# ESP12_RGBW_01.net
KiCad netlist of a schematic drawn in Altium Designer
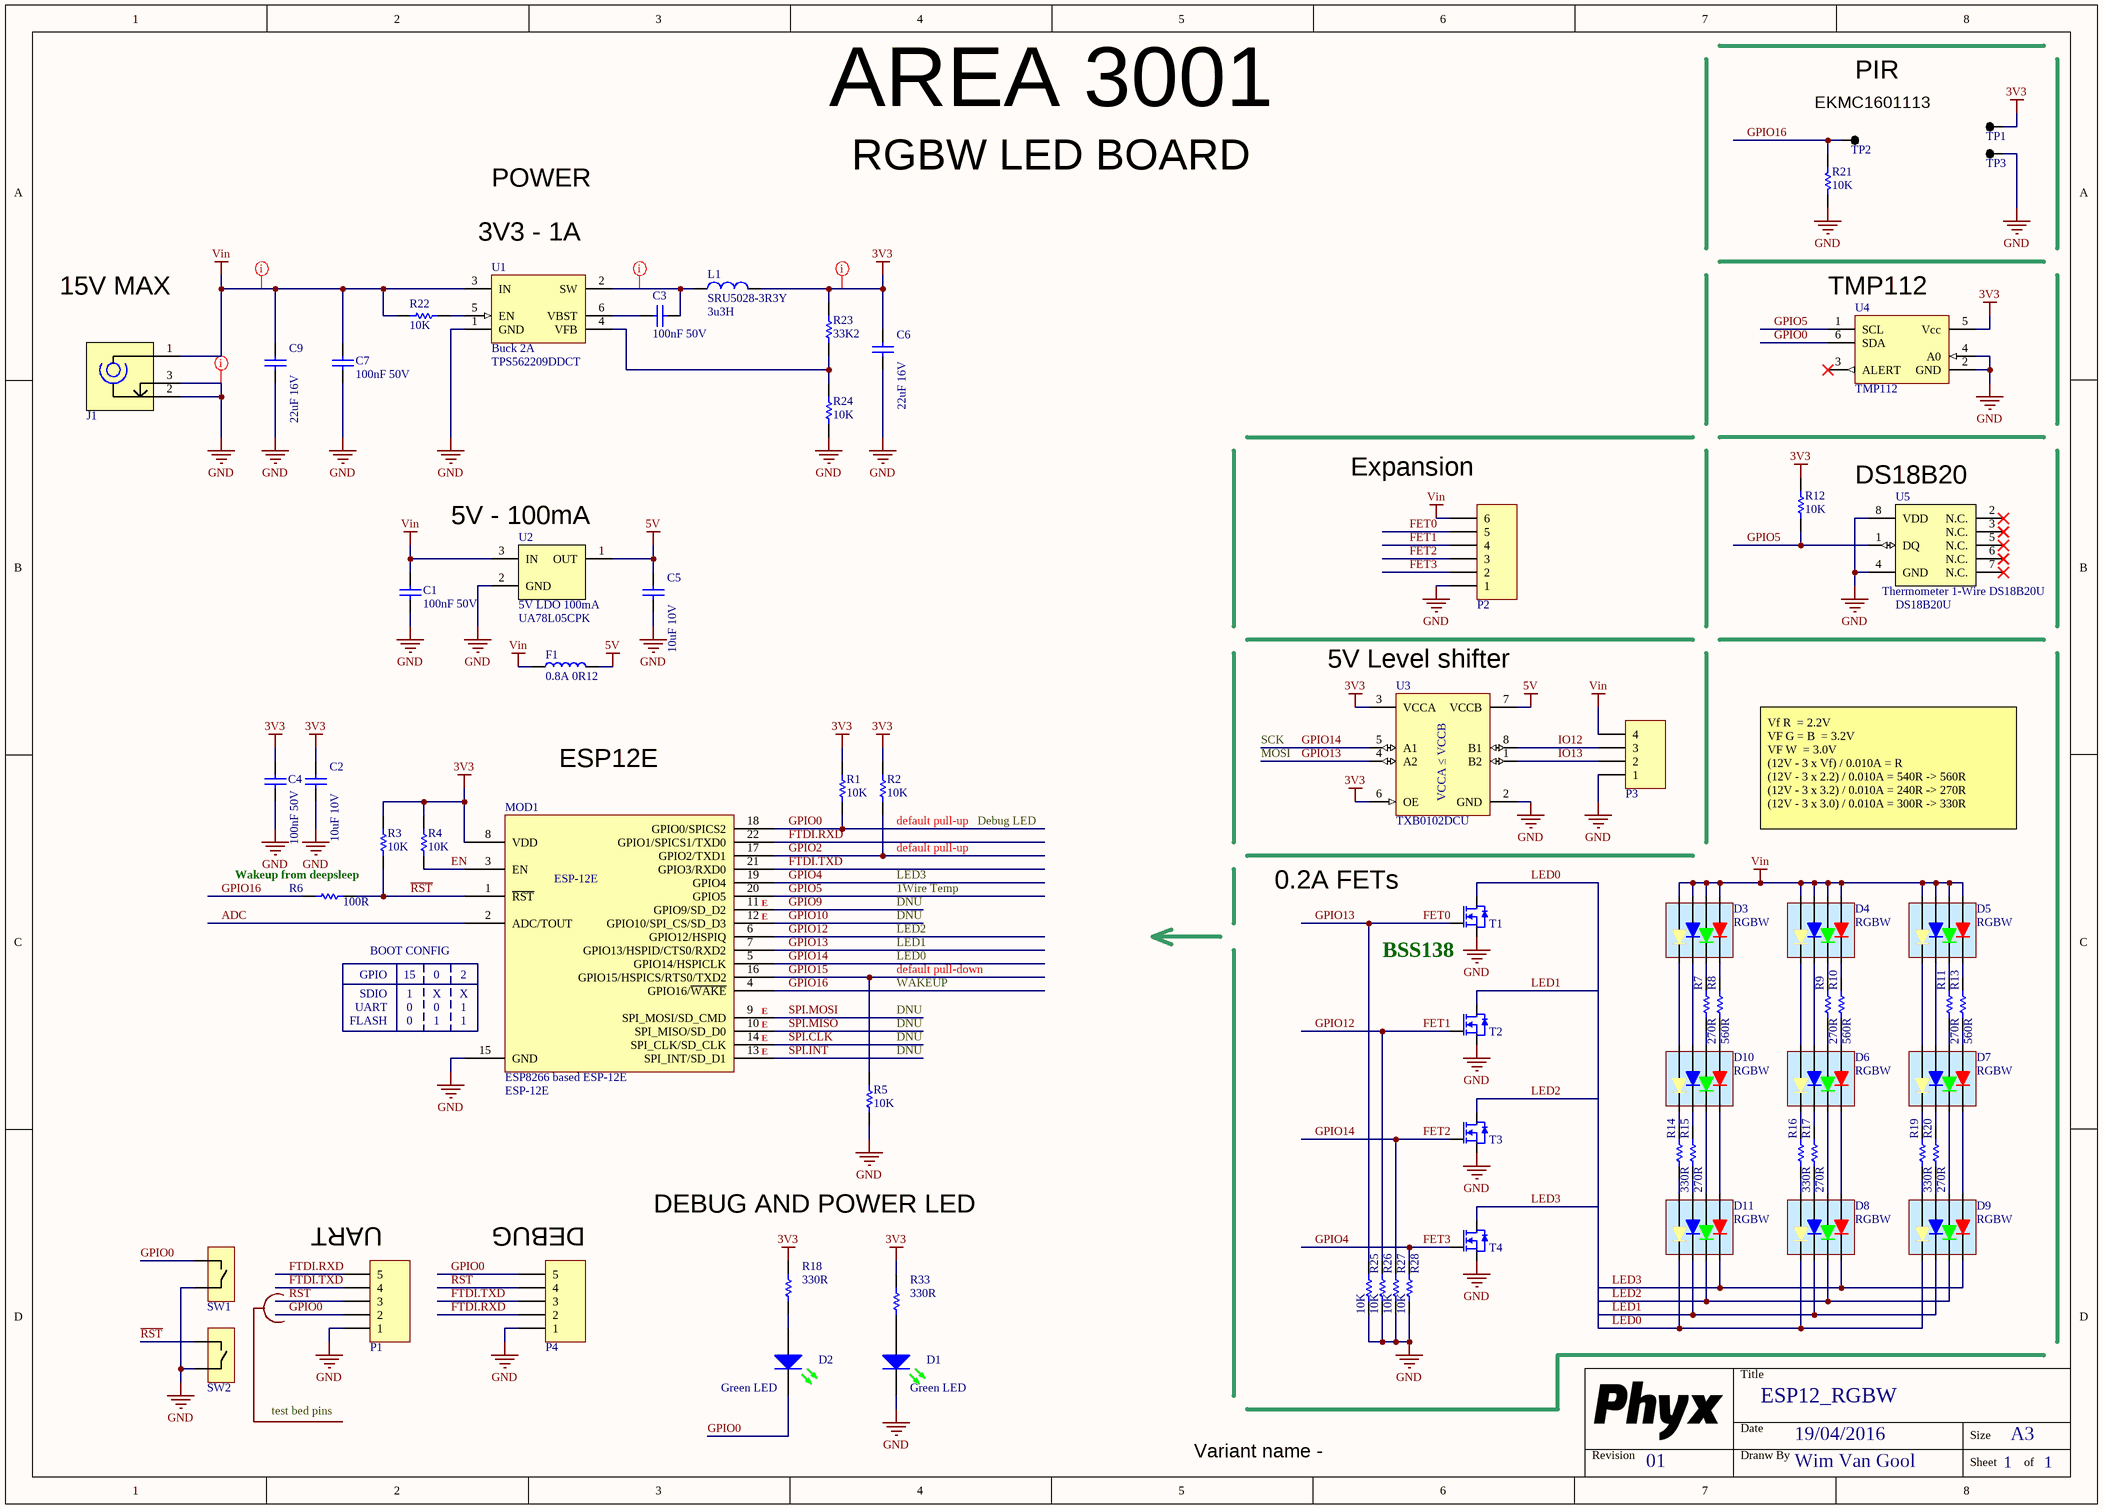
[diagram p0: ESP12_RGBW_01.SchDoc]

(export (version "E")
  (design (tool "Eeschema 10.0.6"))
  (components
    (comp (ref "C1")
      (value "100nF 50V")
      (footprint "C0603_N")
      (description "Capacitor Ceramic")
      (fields (field (name "Comment") "CAP_CERAMIC"))
      (libsource (lib "Phyx_Components") (part "CAP_CERAMIC"))
    )
    (comp (ref "C2")
      (value "10uF 10V")
      (footprint "C0805_N")
      (description "Capacitor Ceramic")
      (fields (field (name "Comment") "CAP_CERAMIC"))
      (libsource (lib "Phyx_Components") (part "CAP_CERAMIC"))
    )
    (comp (ref "C3")
      (value "100nF 50V")
      (footprint "C0603_N")
      (description "Capacitor Ceramic")
      (fields (field (name "Comment") "CAP_CERAMIC"))
      (libsource (lib "Phyx_Components") (part "CAP_CERAMIC"))
    )
    (comp (ref "C4")
      (value "100nF 50V")
      (footprint "C0603_N")
      (description "Capacitor Ceramic")
      (fields (field (name "Comment") "CAP_CERAMIC"))
      (libsource (lib "Phyx_Components") (part "CAP_CERAMIC"))
    )
    (comp (ref "C5")
      (value "10uF 10V")
      (footprint "C0805_N")
      (description "Capacitor Ceramic")
      (fields (field (name "Comment") "CAP_CERAMIC"))
      (libsource (lib "Phyx_Components") (part "CAP_CERAMIC"))
    )
    (comp (ref "C6")
      (value "22uF 16V")
      (footprint "C1206_N")
      (description "Capacitor Ceramic")
      (fields (field (name "Comment") "CAP_CERAMIC"))
      (libsource (lib "Phyx_Components") (part "CAP_CERAMIC"))
    )
    (comp (ref "C7")
      (value "100nF 50V")
      (footprint "C0603_N")
      (description "Capacitor Ceramic")
      (fields (field (name "Comment") "CAP_CERAMIC"))
      (libsource (lib "Phyx_Components") (part "CAP_CERAMIC"))
    )
    (comp (ref "C9")
      (value "22uF 16V")
      (footprint "C1206_N")
      (description "Capacitor Ceramic")
      (fields (field (name "Comment") "CAP_CERAMIC"))
      (libsource (lib "Phyx_Components") (part "CAP_CERAMIC"))
    )
    (comp (ref "D1")
      (value "Green LED")
      (footprint "LED_0805_GR")
      (description "=Description")
      (libsource (lib "Phyx_Components") (part "LED_GREEN"))
    )
    (comp (ref "D2")
      (value "Green LED")
      (footprint "LED_0805_GR")
      (description "=Description")
      (libsource (lib "Phyx_Components") (part "LED_GREEN"))
    )
    (comp (ref "D3")
      (value "RGBW")
      (footprint "LED_5050_RGBW_PLCC8")
      (description "=Description")
      (fields (field (name "Comment") "5050 RGBW LED"))
      (libsource (lib "Phyx_Components") (part "LED_RGBW"))
    )
    (comp (ref "D4")
      (value "RGBW")
      (footprint "LED_5050_RGBW_PLCC8")
      (description "=Description")
      (fields (field (name "Comment") "5050 RGBW LED"))
      (libsource (lib "Phyx_Components") (part "LED_RGBW"))
    )
    (comp (ref "D5")
      (value "RGBW")
      (footprint "LED_5050_RGBW_PLCC8")
      (description "=Description")
      (fields (field (name "Comment") "5050 RGBW LED"))
      (libsource (lib "Phyx_Components") (part "LED_RGBW"))
    )
    (comp (ref "D6")
      (value "RGBW")
      (footprint "LED_5050_RGBW_PLCC8")
      (description "=Description")
      (fields (field (name "Comment") "5050 RGBW LED"))
      (libsource (lib "Phyx_Components") (part "LED_RGBW"))
    )
    (comp (ref "D7")
      (value "RGBW")
      (footprint "LED_5050_RGBW_PLCC8")
      (description "=Description")
      (fields (field (name "Comment") "5050 RGBW LED"))
      (libsource (lib "Phyx_Components") (part "LED_RGBW"))
    )
    (comp (ref "D8")
      (value "RGBW")
      (footprint "LED_5050_RGBW_PLCC8")
      (description "=Description")
      (fields (field (name "Comment") "5050 RGBW LED"))
      (libsource (lib "Phyx_Components") (part "LED_RGBW"))
    )
    (comp (ref "D9")
      (value "RGBW")
      (footprint "LED_5050_RGBW_PLCC8")
      (description "=Description")
      (fields (field (name "Comment") "5050 RGBW LED"))
      (libsource (lib "Phyx_Components") (part "LED_RGBW"))
    )
    (comp (ref "D10")
      (value "RGBW")
      (footprint "LED_5050_RGBW_PLCC8")
      (description "=Description")
      (fields (field (name "Comment") "5050 RGBW LED"))
      (libsource (lib "Phyx_Components") (part "LED_RGBW"))
    )
    (comp (ref "D11")
      (value "RGBW")
      (footprint "LED_5050_RGBW_PLCC8")
      (description "=Description")
      (fields (field (name "Comment") "5050 RGBW LED"))
      (libsource (lib "Phyx_Components") (part "LED_RGBW"))
    )
    (comp (ref "F1")
      (value "0.8A 0R12")
      (footprint "L0805")
      (fields (field (name "Comment") "FERRITE"))
      (libsource (lib "Phyx_Components") (part "FERRITE"))
    )
    (comp (ref "J1")
      (value "Socket RA 3.5 with 1.35 barrel")
      (footprint "DC-003")
      (description "SCKT 1.35mm barrel 3.5mm dia")
      (libsource (lib "Phyx_Components") (part "Cliff_DC10"))
    )
    (comp (ref "L1")
      (value "SRU5028-3R3Y")
      (footprint "BRNS_SRU5028")
      (fields (field (name "ALTIUM_VALUE") "3u3H"))
      (libsource (lib "Phyx_Components") (part "INDUCTOR"))
    )
    (comp (ref "MOD1")
      (value "ESP8266 based ESP-12E")
      (footprint "ESP-12E")
      (description "=Description")
      (fields (field (name "ALTIUM_VALUE") "ESP-12E"))
      (libsource (lib "Phyx_Components") (part "ESP-12E"))
    )
    (comp (ref "P1")
      (value "Header 5")
      (footprint "HDR1X5")
      (libsource (lib "Phyx_Components") (part "Header 5"))
    )
    (comp (ref "P2")
      (value "Header 6")
      (footprint "HDR1X6")
      (libsource (lib "Phyx_Components") (part "Header 6"))
    )
    (comp (ref "P3")
      (value "Header 4")
      (footprint "HDR1X4")
      (libsource (lib "Phyx_Components") (part "Header 4"))
    )
    (comp (ref "P4")
      (value "Header 1.0mm RA Shrouded 5")
      (footprint "WE_665105131822")
      (libsource (lib "Phyx_Components") (part "Header 5"))
    )
    (comp (ref "R1")
      (value "10K")
      (footprint "R0603_N")
      (fields (field (name "Comment") "RESISTOR"))
      (libsource (lib "Phyx_Components") (part "RESISTOR"))
    )
    (comp (ref "R2")
      (value "10K")
      (footprint "R0603_N")
      (fields (field (name "Comment") "RESISTOR"))
      (libsource (lib "Phyx_Components") (part "RESISTOR"))
    )
    (comp (ref "R3")
      (value "10K")
      (footprint "R0603_N")
      (fields (field (name "Comment") "RESISTOR"))
      (libsource (lib "Phyx_Components") (part "RESISTOR"))
    )
    (comp (ref "R4")
      (value "10K")
      (footprint "R0603_N")
      (fields (field (name "Comment") "RESISTOR"))
      (libsource (lib "Phyx_Components") (part "RESISTOR"))
    )
    (comp (ref "R5")
      (value "10K")
      (footprint "R0603_N")
      (fields (field (name "Comment") "RESISTOR"))
      (libsource (lib "Phyx_Components") (part "RESISTOR"))
    )
    (comp (ref "R6")
      (value "100R")
      (footprint "R0603_N")
      (fields (field (name "Comment") "RESISTOR"))
      (libsource (lib "Phyx_Components") (part "RESISTOR"))
    )
    (comp (ref "R7")
      (value "270R")
      (footprint "R0603_N")
      (fields (field (name "Comment") "RESISTOR"))
      (libsource (lib "Phyx_Components") (part "RESISTOR"))
    )
    (comp (ref "R8")
      (value "560R")
      (footprint "R0603_N")
      (fields (field (name "Comment") "RESISTOR"))
      (libsource (lib "Phyx_Components") (part "RESISTOR"))
    )
    (comp (ref "R9")
      (value "270R")
      (footprint "R0603_N")
      (fields (field (name "Comment") "RESISTOR"))
      (libsource (lib "Phyx_Components") (part "RESISTOR"))
    )
    (comp (ref "R10")
      (value "560R")
      (footprint "R0603_N")
      (fields (field (name "Comment") "RESISTOR"))
      (libsource (lib "Phyx_Components") (part "RESISTOR"))
    )
    (comp (ref "R11")
      (value "270R")
      (footprint "R0603_N")
      (fields (field (name "Comment") "RESISTOR"))
      (libsource (lib "Phyx_Components") (part "RESISTOR"))
    )
    (comp (ref "R12")
      (value "10K")
      (footprint "R0603_N")
      (fields (field (name "Comment") "RESISTOR"))
      (libsource (lib "Phyx_Components") (part "RESISTOR"))
    )
    (comp (ref "R13")
      (value "560R")
      (footprint "R0603_N")
      (fields (field (name "Comment") "RESISTOR"))
      (libsource (lib "Phyx_Components") (part "RESISTOR"))
    )
    (comp (ref "R14")
      (value "330R")
      (footprint "R0603_N")
      (fields (field (name "Comment") "RESISTOR"))
      (libsource (lib "Phyx_Components") (part "RESISTOR"))
    )
    (comp (ref "R15")
      (value "270R")
      (footprint "R0603_N")
      (fields (field (name "Comment") "RESISTOR"))
      (libsource (lib "Phyx_Components") (part "RESISTOR"))
    )
    (comp (ref "R16")
      (value "330R")
      (footprint "R0603_N")
      (fields (field (name "Comment") "RESISTOR"))
      (libsource (lib "Phyx_Components") (part "RESISTOR"))
    )
    (comp (ref "R17")
      (value "270R")
      (footprint "R0603_N")
      (fields (field (name "Comment") "RESISTOR"))
      (libsource (lib "Phyx_Components") (part "RESISTOR"))
    )
    (comp (ref "R18")
      (value "330R")
      (footprint "R0603_N")
      (fields (field (name "Comment") "RESISTOR"))
      (libsource (lib "Phyx_Components") (part "RESISTOR"))
    )
    (comp (ref "R19")
      (value "330R")
      (footprint "R0603_N")
      (fields (field (name "Comment") "RESISTOR"))
      (libsource (lib "Phyx_Components") (part "RESISTOR"))
    )
    (comp (ref "R20")
      (value "270R")
      (footprint "R0603_N")
      (fields (field (name "Comment") "RESISTOR"))
      (libsource (lib "Phyx_Components") (part "RESISTOR"))
    )
    (comp (ref "R21")
      (value "10K")
      (footprint "R0603_N")
      (fields (field (name "Comment") "RESISTOR"))
      (libsource (lib "Phyx_Components") (part "RESISTOR"))
    )
    (comp (ref "R22")
      (value "10K")
      (footprint "R0603_N")
      (fields (field (name "Comment") "RESISTOR"))
      (libsource (lib "Phyx_Components") (part "RESISTOR"))
    )
    (comp (ref "R23")
      (value "33K2")
      (footprint "R0603_N")
      (fields (field (name "Comment") "RESISTOR"))
      (libsource (lib "Phyx_Components") (part "RESISTOR"))
    )
    (comp (ref "R24")
      (value "10K")
      (footprint "R0603_N")
      (fields (field (name "Comment") "RESISTOR"))
      (libsource (lib "Phyx_Components") (part "RESISTOR"))
    )
    (comp (ref "R25")
      (value "10K")
      (footprint "R0603_N")
      (fields (field (name "Comment") "RESISTOR"))
      (libsource (lib "Phyx_Components") (part "RESISTOR"))
    )
    (comp (ref "R26")
      (value "10K")
      (footprint "R0603_N")
      (fields (field (name "Comment") "RESISTOR"))
      (libsource (lib "Phyx_Components") (part "RESISTOR"))
    )
    (comp (ref "R27")
      (value "10K")
      (footprint "R0603_N")
      (fields (field (name "Comment") "RESISTOR"))
      (libsource (lib "Phyx_Components") (part "RESISTOR"))
    )
    (comp (ref "R28")
      (value "10K")
      (footprint "R0603_N")
      (fields (field (name "Comment") "RESISTOR"))
      (libsource (lib "Phyx_Components") (part "RESISTOR"))
    )
    (comp (ref "R33")
      (value "330R")
      (footprint "R0603_N")
      (fields (field (name "Comment") "RESISTOR"))
      (libsource (lib "Phyx_Components") (part "RESISTOR"))
    )
    (comp (ref "SW1")
      (value "LP SMD tact sw")
      (footprint "CK_KMR4")
      (libsource (lib "Phyx_Components") (part "SW_TACT"))
    )
    (comp (ref "SW2")
      (value "LP SMD tact sw")
      (footprint "CK_KMR4")
      (libsource (lib "Phyx_Components") (part "SW_TACT"))
    )
    (comp (ref "T1")
      (value "0.2A N-Ch MOSFET Vgs 3.2")
      (footprint "SOT23-3")
      (description "BSS138 N-Ch MOSFET 0.2A 3.2Vgs 60Vds")
      (libsource (lib "Phyx_Components") (part "N_MOSFET_GSD"))
    )
    (comp (ref "T2")
      (value "0.2A N-Ch MOSFET Vgs 3.2")
      (footprint "SOT23-3")
      (description "BSS138 N-Ch MOSFET 0.2A 3.2Vgs 60Vds")
      (libsource (lib "Phyx_Components") (part "N_MOSFET_GSD"))
    )
    (comp (ref "T3")
      (value "0.2A N-Ch MOSFET Vgs 3.2")
      (footprint "SOT23-3")
      (description "BSS138 N-Ch MOSFET 0.2A 3.2Vgs 60Vds")
      (libsource (lib "Phyx_Components") (part "N_MOSFET_GSD"))
    )
    (comp (ref "T4")
      (value "0.2A N-Ch MOSFET Vgs 3.2")
      (footprint "SOT23-3")
      (description "BSS138 N-Ch MOSFET 0.2A 3.2Vgs 60Vds")
      (libsource (lib "Phyx_Components") (part "N_MOSFET_GSD"))
    )
    (comp (ref "TP1")
      (value "TEST_PAD")
      (footprint "TP_0.8mm_0.4mm")
      (libsource (lib "Phyx_Components") (part "TEST_PAD"))
    )
    (comp (ref "TP2")
      (value "TEST_PAD")
      (footprint "TP_0.8mm_0.4mm")
      (libsource (lib "Phyx_Components") (part "TEST_PAD"))
    )
    (comp (ref "TP3")
      (value "TEST_PAD")
      (footprint "TP_0.8mm_0.4mm")
      (libsource (lib "Phyx_Components") (part "TEST_PAD"))
    )
    (comp (ref "U1")
      (value "Buck 2A")
      (footprint "TI_DDC_R-PDSO-G6")
      (description "=Description")
      (fields (field (name "ALTIUM_VALUE") "TPS562209DDCT"))
      (libsource (lib "Phyx_Components") (part "TPS56x209"))
    )
    (comp (ref "U2")
      (value "5V LDO 100mA")
      (footprint "TI_PK")
      (description "LDO 5V 100mA")
      (fields (field (name "ALTIUM_VALUE") "UA78L05CPK"))
      (libsource (lib "Phyx_Components") (part "UA78L05CPK"))
    )
    (comp (ref "U3")
      (value "TXB0102DCU")
      (footprint "TI_DCU_R-PDSO-G8")
      (description "=Description")
      (fields (field (name "Comment") "2-bit Bi Level translator, 15kV ESD"))
      (libsource (lib "Phyx_Components") (part "TXB0102DCU"))
    )
    (comp (ref "U4")
      (value "TMP112")
      (footprint "TI_DRL_R-PDSO-N6")
      (description "=Description")
      (fields (field (name "Comment") "I2C Temp sensor High Accuracy"))
      (libsource (lib "Phyx_Components") (part "TMP1x2"))
    )
    (comp (ref "U5")
      (value "Thermometer 1-Wire DS18B20U")
      (footprint "MAX_uSOP8")
      (description "=Description")
      (fields (field (name "ALTIUM_VALUE") "DS18B20U"))
      (libsource (lib "Phyx_Components") (part "DS18B20U"))
    )
  )
  (nets
    (net (code "1") (name "/ADC") (class "Default")
      (node (ref "MOD1") (pin "2") (pinfunction "ADC/TOUT_2") (pintype "passive"))
    )
    (net (code "2") (name "/EN") (class "Default")
      (node (ref "MOD1") (pin "3") (pinfunction "EN_3") (pintype "passive"))
      (node (ref "R4") (pin "2") (pinfunction "2_2") (pintype "passive"))
    )
    (net (code "3") (name "/FET0") (class "Default")
      (node (ref "MOD1") (pin "7") (pinfunction "GPIO13/HSPID/CTS0/RXD2_7") (pintype "passive"))
      (node (ref "P2") (pin "5") (pinfunction "5_5") (pintype "passive"))
      (node (ref "R25") (pin "1") (pinfunction "1_1") (pintype "passive"))
      (node (ref "T1") (pin "1") (pinfunction "G_1") (pintype "passive"))
      (node (ref "U3") (pin "4") (pinfunction "A2_4") (pintype "bidirectional"))
    )
    (net (code "4") (name "/FET1") (class "Default")
      (node (ref "MOD1") (pin "6") (pinfunction "GPIO12/HSPIQ_6") (pintype "passive"))
      (node (ref "P2") (pin "4") (pinfunction "4_4") (pintype "passive"))
      (node (ref "R26") (pin "1") (pinfunction "1_1") (pintype "passive"))
      (node (ref "T2") (pin "1") (pinfunction "G_1") (pintype "passive"))
    )
    (net (code "5") (name "/FET2") (class "Default")
      (node (ref "MOD1") (pin "5") (pinfunction "GPIO14/HSPICLK_5") (pintype "passive"))
      (node (ref "P2") (pin "3") (pinfunction "3_3") (pintype "passive"))
      (node (ref "R27") (pin "1") (pinfunction "1_1") (pintype "passive"))
      (node (ref "T3") (pin "1") (pinfunction "G_1") (pintype "passive"))
      (node (ref "U3") (pin "5") (pinfunction "A1_5") (pintype "bidirectional"))
    )
    (net (code "6") (name "/FET3") (class "Default")
      (node (ref "MOD1") (pin "19") (pinfunction "GPIO4_19") (pintype "passive"))
      (node (ref "P2") (pin "2") (pinfunction "2_2") (pintype "passive"))
      (node (ref "R28") (pin "1") (pinfunction "1_1") (pintype "passive"))
      (node (ref "T4") (pin "1") (pinfunction "G_1") (pintype "passive"))
    )
    (net (code "7") (name "/FTDI.RXD") (class "Default")
      (node (ref "MOD1") (pin "22") (pinfunction "GPIO1/SPICS1/TXD0_22") (pintype "passive"))
      (node (ref "P1") (pin "5") (pinfunction "5_5") (pintype "passive"))
      (node (ref "P4") (pin "2") (pinfunction "2_2") (pintype "passive"))
    )
    (net (code "8") (name "/FTDI.TXD") (class "Default")
      (node (ref "MOD1") (pin "21") (pinfunction "GPIO3/RXD0_21") (pintype "passive"))
      (node (ref "P1") (pin "4") (pinfunction "4_4") (pintype "passive"))
      (node (ref "P4") (pin "3") (pinfunction "3_3") (pintype "passive"))
    )
    (net (code "9") (name "/GPIO0") (class "Default")
      (node (ref "D2") (pin "2") (pinfunction "K_2") (pintype "passive"))
      (node (ref "MOD1") (pin "18") (pinfunction "GPIO0/SPICS2_18") (pintype "passive"))
      (node (ref "P1") (pin "2") (pinfunction "2_2") (pintype "passive"))
      (node (ref "P4") (pin "5") (pinfunction "5_5") (pintype "passive"))
      (node (ref "R1") (pin "2") (pinfunction "2_2") (pintype "passive"))
      (node (ref "SW1") (pin "1") (pinfunction "1_1") (pintype "passive"))
      (node (ref "U4") (pin "6") (pinfunction "SDA_6") (pintype "open_collector"))
    )
    (net (code "10") (name "/GPIO2") (class "Default")
      (node (ref "MOD1") (pin "17") (pinfunction "GPIO2/TXD1_17") (pintype "passive"))
      (node (ref "R2") (pin "2") (pinfunction "2_2") (pintype "passive"))
    )
    (net (code "11") (name "/GPIO5") (class "Default")
      (node (ref "MOD1") (pin "20") (pinfunction "GPIO5_20") (pintype "passive"))
      (node (ref "R12") (pin "2") (pinfunction "2_2") (pintype "passive"))
      (node (ref "U4") (pin "1") (pinfunction "SCL_1") (pintype "open_collector"))
      (node (ref "U5") (pin "1") (pinfunction "DQ_1") (pintype "bidirectional"))
    )
    (net (code "12") (name "/GPIO9") (class "Default")
      (node (ref "MOD1") (pin "11") (pinfunction "GPIO9/SD_D2_11") (pintype "passive"))
    )
    (net (code "13") (name "/GPIO10") (class "Default")
      (node (ref "MOD1") (pin "12") (pinfunction "GPIO10/SPI_CS/SD_D3_12") (pintype "passive"))
    )
    (net (code "14") (name "/GPIO15") (class "Default")
      (node (ref "MOD1") (pin "16") (pinfunction "GPIO15/HSPICS/RTS0/TXD2_16") (pintype "passive"))
      (node (ref "R5") (pin "1") (pinfunction "1_1") (pintype "passive"))
    )
    (net (code "15") (name "/GPIO16") (class "Default")
      (node (ref "MOD1") (pin "4") (pinfunction "GPIO16/~{WAKE}_4") (pintype "passive"))
      (node (ref "R21") (pin "1") (pinfunction "1_1") (pintype "passive"))
      (node (ref "R6") (pin "2") (pinfunction "2_2") (pintype "passive"))
      (node (ref "TP2") (pin "1") (pinfunction "1_1") (pintype "passive"))
    )
    (net (code "16") (name "/IO12") (class "Default")
      (node (ref "P3") (pin "3") (pinfunction "3_3") (pintype "passive"))
      (node (ref "U3") (pin "8") (pinfunction "B1_8") (pintype "bidirectional"))
    )
    (net (code "17") (name "/IO13") (class "Default")
      (node (ref "P3") (pin "2") (pinfunction "2_2") (pintype "passive"))
      (node (ref "U3") (pin "1") (pinfunction "B2_1") (pintype "bidirectional"))
    )
    (net (code "18") (name "/LED0") (class "Default")
      (node (ref "D11") (pin "8") (pinfunction "WC_8") (pintype "passive"))
      (node (ref "D8") (pin "8") (pinfunction "WC_8") (pintype "passive"))
      (node (ref "D9") (pin "8") (pinfunction "WC_8") (pintype "passive"))
      (node (ref "T1") (pin "3") (pinfunction "D_3") (pintype "passive"))
    )
    (net (code "19") (name "/LED1") (class "Default")
      (node (ref "D11") (pin "6") (pinfunction "BC_6") (pintype "passive"))
      (node (ref "D8") (pin "6") (pinfunction "BC_6") (pintype "passive"))
      (node (ref "D9") (pin "6") (pinfunction "BC_6") (pintype "passive"))
      (node (ref "T2") (pin "3") (pinfunction "D_3") (pintype "passive"))
    )
    (net (code "20") (name "/LED2") (class "Default")
      (node (ref "D11") (pin "4") (pinfunction "GC_4") (pintype "passive"))
      (node (ref "D8") (pin "4") (pinfunction "GC_4") (pintype "passive"))
      (node (ref "D9") (pin "4") (pinfunction "GC_4") (pintype "passive"))
      (node (ref "T3") (pin "3") (pinfunction "D_3") (pintype "passive"))
    )
    (net (code "21") (name "/LED3") (class "Default")
      (node (ref "D11") (pin "2") (pinfunction "RC_2") (pintype "passive"))
      (node (ref "D8") (pin "2") (pinfunction "RC_2") (pintype "passive"))
      (node (ref "D9") (pin "2") (pinfunction "RC_2") (pintype "passive"))
      (node (ref "T4") (pin "3") (pinfunction "D_3") (pintype "passive"))
    )
    (net (code "22") (name "/SPI.CLK") (class "Default")
      (node (ref "MOD1") (pin "14") (pinfunction "SPI_CLK/SD_CLK_14") (pintype "passive"))
    )
    (net (code "23") (name "/SPI.INT") (class "Default")
      (node (ref "MOD1") (pin "13") (pinfunction "SPI_INT/SD_D1_13") (pintype "passive"))
    )
    (net (code "24") (name "/SPI.MISO") (class "Default")
      (node (ref "MOD1") (pin "10") (pinfunction "SPI_MISO/SD_D0_10") (pintype "passive"))
    )
    (net (code "25") (name "/SPI.MOSI") (class "Default")
      (node (ref "MOD1") (pin "9") (pinfunction "SPI_MOSI/SD_CMD_9") (pintype "passive"))
    )
    (net (code "26") (name "/~{RST}") (class "Default")
      (node (ref "MOD1") (pin "1") (pinfunction "~{RST}_1") (pintype "passive"))
      (node (ref "P1") (pin "3") (pinfunction "3_3") (pintype "passive"))
      (node (ref "P4") (pin "4") (pinfunction "4_4") (pintype "passive"))
      (node (ref "R3") (pin "2") (pinfunction "2_2") (pintype "passive"))
      (node (ref "R6") (pin "1") (pinfunction "1_1") (pintype "passive"))
      (node (ref "SW2") (pin "1") (pinfunction "1_1") (pintype "passive"))
    )
    (net (code "27") (name "3V3") (class "Default")
      (node (ref "C2") (pin "1") (pinfunction "1_1") (pintype "passive"))
      (node (ref "C4") (pin "1") (pinfunction "1_1") (pintype "passive"))
      (node (ref "C6") (pin "1") (pinfunction "1_1") (pintype "passive"))
      (node (ref "L1") (pin "2") (pinfunction "2_2") (pintype "passive"))
      (node (ref "MOD1") (pin "8") (pinfunction "VDD_8") (pintype "passive"))
      (node (ref "R1") (pin "1") (pinfunction "1_1") (pintype "passive"))
      (node (ref "R12") (pin "1") (pinfunction "1_1") (pintype "passive"))
      (node (ref "R18") (pin "1") (pinfunction "1_1") (pintype "passive"))
      (node (ref "R2") (pin "1") (pinfunction "1_1") (pintype "passive"))
      (node (ref "R23") (pin "1") (pinfunction "1_1") (pintype "passive"))
      (node (ref "R3") (pin "1") (pinfunction "1_1") (pintype "passive"))
      (node (ref "R33") (pin "1") (pinfunction "1_1") (pintype "passive"))
      (node (ref "R4") (pin "1") (pinfunction "1_1") (pintype "passive"))
      (node (ref "TP1") (pin "1") (pinfunction "1_1") (pintype "passive"))
      (node (ref "U3") (pin "3") (pinfunction "VCCA_3") (pintype "power_in"))
      (node (ref "U3") (pin "6") (pinfunction "OE_6") (pintype "input"))
      (node (ref "U4") (pin "5") (pinfunction "Vcc_5") (pintype "power_in"))
    )
    (net (code "28") (name "5V") (class "Default")
      (node (ref "C5") (pin "1") (pinfunction "1_1") (pintype "passive"))
      (node (ref "F1") (pin "2") (pinfunction "2_2") (pintype "passive"))
      (node (ref "U2") (pin "1") (pinfunction "OUT_1") (pintype "passive"))
      (node (ref "U3") (pin "7") (pinfunction "VCCB_7") (pintype "power_in"))
    )
    (net (code "29") (name "GND") (class "Default")
      (node (ref "C1") (pin "2") (pinfunction "2_2") (pintype "passive"))
      (node (ref "C2") (pin "2") (pinfunction "2_2") (pintype "passive"))
      (node (ref "C4") (pin "2") (pinfunction "2_2") (pintype "passive"))
      (node (ref "C5") (pin "2") (pinfunction "2_2") (pintype "passive"))
      (node (ref "C6") (pin "2") (pinfunction "2_2") (pintype "passive"))
      (node (ref "C7") (pin "1") (pinfunction "1_1") (pintype "passive"))
      (node (ref "C9") (pin "2") (pinfunction "2_2") (pintype "passive"))
      (node (ref "D1") (pin "2") (pinfunction "K_2") (pintype "passive"))
      (node (ref "J1") (pin "2") (pinfunction "2_2") (pintype "passive"))
      (node (ref "J1") (pin "3") (pinfunction "3_3") (pintype "passive"))
      (node (ref "MOD1") (pin "15") (pinfunction "GND_15") (pintype "passive"))
      (node (ref "P1") (pin "1") (pinfunction "1_1") (pintype "passive"))
      (node (ref "P2") (pin "1") (pinfunction "1_1") (pintype "passive"))
      (node (ref "P3") (pin "1") (pinfunction "1_1") (pintype "passive"))
      (node (ref "P4") (pin "1") (pinfunction "1_1") (pintype "passive"))
      (node (ref "R21") (pin "2") (pinfunction "2_2") (pintype "passive"))
      (node (ref "R24") (pin "2") (pinfunction "2_2") (pintype "passive"))
      (node (ref "R25") (pin "2") (pinfunction "2_2") (pintype "passive"))
      (node (ref "R26") (pin "2") (pinfunction "2_2") (pintype "passive"))
      (node (ref "R27") (pin "2") (pinfunction "2_2") (pintype "passive"))
      (node (ref "R28") (pin "2") (pinfunction "2_2") (pintype "passive"))
      (node (ref "R5") (pin "2") (pinfunction "2_2") (pintype "passive"))
      (node (ref "SW1") (pin "2") (pinfunction "2_2") (pintype "passive"))
      (node (ref "SW2") (pin "2") (pinfunction "2_2") (pintype "passive"))
      (node (ref "T1") (pin "2") (pinfunction "S_2") (pintype "passive"))
      (node (ref "T2") (pin "2") (pinfunction "S_2") (pintype "passive"))
      (node (ref "T3") (pin "2") (pinfunction "S_2") (pintype "passive"))
      (node (ref "T4") (pin "2") (pinfunction "S_2") (pintype "passive"))
      (node (ref "TP3") (pin "1") (pinfunction "1_1") (pintype "passive"))
      (node (ref "U1") (pin "1") (pinfunction "GND_1") (pintype "power_in"))
      (node (ref "U2") (pin "2") (pinfunction "GND_2") (pintype "passive"))
      (node (ref "U3") (pin "2") (pinfunction "GND_2") (pintype "power_in"))
      (node (ref "U4") (pin "2") (pinfunction "GND_2") (pintype "power_in"))
      (node (ref "U4") (pin "4") (pinfunction "A0_4") (pintype "input"))
      (node (ref "U5") (pin "4") (pinfunction "GND_4") (pintype "power_in"))
      (node (ref "U5") (pin "8") (pinfunction "VDD_8") (pintype "power_in"))
    )
    (net (code "30") (name "Net-(D1-A)") (class "Default")
      (node (ref "D1") (pin "1") (pinfunction "A_1") (pintype "passive"))
      (node (ref "R33") (pin "2") (pinfunction "2_2") (pintype "passive"))
    )
    (net (code "31") (name "Net-(D2-A)") (class "Default")
      (node (ref "D2") (pin "1") (pinfunction "A_1") (pintype "passive"))
      (node (ref "R18") (pin "2") (pinfunction "2_2") (pintype "passive"))
    )
    (net (code "32") (name "Net-(D3-GC)") (class "Default")
      (node (ref "D3") (pin "4") (pinfunction "GC_4") (pintype "passive"))
      (node (ref "R7") (pin "1") (pinfunction "1_1") (pintype "passive"))
    )
    (net (code "33") (name "Net-(D3-RC)") (class "Default")
      (node (ref "D3") (pin "2") (pinfunction "RC_2") (pintype "passive"))
      (node (ref "R8") (pin "1") (pinfunction "1_1") (pintype "passive"))
    )
    (net (code "34") (name "Net-(D4-BC)") (class "Default")
      (node (ref "D4") (pin "6") (pinfunction "BC_6") (pintype "passive"))
      (node (ref "D6") (pin "5") (pinfunction "BA_5") (pintype "passive"))
    )
    (net (code "35") (name "Net-(D4-GC)") (class "Default")
      (node (ref "D4") (pin "4") (pinfunction "GC_4") (pintype "passive"))
      (node (ref "R9") (pin "1") (pinfunction "1_1") (pintype "passive"))
    )
    (net (code "36") (name "Net-(D4-RC)") (class "Default")
      (node (ref "D4") (pin "2") (pinfunction "RC_2") (pintype "passive"))
      (node (ref "R10") (pin "1") (pinfunction "1_1") (pintype "passive"))
    )
    (net (code "37") (name "Net-(D4-WC)") (class "Default")
      (node (ref "D4") (pin "8") (pinfunction "WC_8") (pintype "passive"))
      (node (ref "D6") (pin "7") (pinfunction "WA_7") (pintype "passive"))
    )
    (net (code "38") (name "Net-(D5-BC)") (class "Default")
      (node (ref "D5") (pin "6") (pinfunction "BC_6") (pintype "passive"))
      (node (ref "D7") (pin "5") (pinfunction "BA_5") (pintype "passive"))
    )
    (net (code "39") (name "Net-(D5-GC)") (class "Default")
      (node (ref "D5") (pin "4") (pinfunction "GC_4") (pintype "passive"))
      (node (ref "R11") (pin "1") (pinfunction "1_1") (pintype "passive"))
    )
    (net (code "40") (name "Net-(D5-RC)") (class "Default")
      (node (ref "D5") (pin "2") (pinfunction "RC_2") (pintype "passive"))
      (node (ref "R13") (pin "1") (pinfunction "1_1") (pintype "passive"))
    )
    (net (code "41") (name "Net-(D5-WC)") (class "Default")
      (node (ref "D5") (pin "8") (pinfunction "WC_8") (pintype "passive"))
      (node (ref "D7") (pin "7") (pinfunction "WA_7") (pintype "passive"))
    )
    (net (code "42") (name "Net-(D6-BC)") (class "Default")
      (node (ref "D6") (pin "6") (pinfunction "BC_6") (pintype "passive"))
      (node (ref "R17") (pin "1") (pinfunction "1_1") (pintype "passive"))
    )
    (net (code "43") (name "Net-(D6-GA)") (class "Default")
      (node (ref "D6") (pin "3") (pinfunction "GA_3") (pintype "passive"))
      (node (ref "R9") (pin "2") (pinfunction "2_2") (pintype "passive"))
    )
    (net (code "44") (name "Net-(D6-GC)") (class "Default")
      (node (ref "D6") (pin "4") (pinfunction "GC_4") (pintype "passive"))
      (node (ref "D8") (pin "3") (pinfunction "GA_3") (pintype "passive"))
    )
    (net (code "45") (name "Net-(D6-RA)") (class "Default")
      (node (ref "D6") (pin "1") (pinfunction "RA_1") (pintype "passive"))
      (node (ref "R10") (pin "2") (pinfunction "2_2") (pintype "passive"))
    )
    (net (code "46") (name "Net-(D6-RC)") (class "Default")
      (node (ref "D6") (pin "2") (pinfunction "RC_2") (pintype "passive"))
      (node (ref "D8") (pin "1") (pinfunction "RA_1") (pintype "passive"))
    )
    (net (code "47") (name "Net-(D6-WC)") (class "Default")
      (node (ref "D6") (pin "8") (pinfunction "WC_8") (pintype "passive"))
      (node (ref "R16") (pin "1") (pinfunction "1_1") (pintype "passive"))
    )
    (net (code "48") (name "Net-(D7-BC)") (class "Default")
      (node (ref "D7") (pin "6") (pinfunction "BC_6") (pintype "passive"))
      (node (ref "R20") (pin "1") (pinfunction "1_1") (pintype "passive"))
    )
    (net (code "49") (name "Net-(D7-GA)") (class "Default")
      (node (ref "D7") (pin "3") (pinfunction "GA_3") (pintype "passive"))
      (node (ref "R11") (pin "2") (pinfunction "2_2") (pintype "passive"))
    )
    (net (code "50") (name "Net-(D7-GC)") (class "Default")
      (node (ref "D7") (pin "4") (pinfunction "GC_4") (pintype "passive"))
      (node (ref "D9") (pin "3") (pinfunction "GA_3") (pintype "passive"))
    )
    (net (code "51") (name "Net-(D7-RA)") (class "Default")
      (node (ref "D7") (pin "1") (pinfunction "RA_1") (pintype "passive"))
      (node (ref "R13") (pin "2") (pinfunction "2_2") (pintype "passive"))
    )
    (net (code "52") (name "Net-(D7-RC)") (class "Default")
      (node (ref "D7") (pin "2") (pinfunction "RC_2") (pintype "passive"))
      (node (ref "D9") (pin "1") (pinfunction "RA_1") (pintype "passive"))
    )
    (net (code "53") (name "Net-(D7-WC)") (class "Default")
      (node (ref "D7") (pin "8") (pinfunction "WC_8") (pintype "passive"))
      (node (ref "R19") (pin "1") (pinfunction "1_1") (pintype "passive"))
    )
    (net (code "54") (name "Net-(D8-BA)") (class "Default")
      (node (ref "D8") (pin "5") (pinfunction "BA_5") (pintype "passive"))
      (node (ref "R17") (pin "2") (pinfunction "2_2") (pintype "passive"))
    )
    (net (code "55") (name "Net-(D8-WA)") (class "Default")
      (node (ref "D8") (pin "7") (pinfunction "WA_7") (pintype "passive"))
      (node (ref "R16") (pin "2") (pinfunction "2_2") (pintype "passive"))
    )
    (net (code "56") (name "Net-(D9-BA)") (class "Default")
      (node (ref "D9") (pin "5") (pinfunction "BA_5") (pintype "passive"))
      (node (ref "R20") (pin "2") (pinfunction "2_2") (pintype "passive"))
    )
    (net (code "57") (name "Net-(D9-WA)") (class "Default")
      (node (ref "D9") (pin "7") (pinfunction "WA_7") (pintype "passive"))
      (node (ref "R19") (pin "2") (pinfunction "2_2") (pintype "passive"))
    )
    (net (code "58") (name "Net-(D10-BA)") (class "Default")
      (node (ref "D10") (pin "5") (pinfunction "BA_5") (pintype "passive"))
      (node (ref "D3") (pin "6") (pinfunction "BC_6") (pintype "passive"))
    )
    (net (code "59") (name "Net-(D10-BC)") (class "Default")
      (node (ref "D10") (pin "6") (pinfunction "BC_6") (pintype "passive"))
      (node (ref "R15") (pin "1") (pinfunction "1_1") (pintype "passive"))
    )
    (net (code "60") (name "Net-(D10-GA)") (class "Default")
      (node (ref "D10") (pin "3") (pinfunction "GA_3") (pintype "passive"))
      (node (ref "R7") (pin "2") (pinfunction "2_2") (pintype "passive"))
    )
    (net (code "61") (name "Net-(D10-GC)") (class "Default")
      (node (ref "D10") (pin "4") (pinfunction "GC_4") (pintype "passive"))
      (node (ref "D11") (pin "3") (pinfunction "GA_3") (pintype "passive"))
    )
    (net (code "62") (name "Net-(D10-RA)") (class "Default")
      (node (ref "D10") (pin "1") (pinfunction "RA_1") (pintype "passive"))
      (node (ref "R8") (pin "2") (pinfunction "2_2") (pintype "passive"))
    )
    (net (code "63") (name "Net-(D10-RC)") (class "Default")
      (node (ref "D10") (pin "2") (pinfunction "RC_2") (pintype "passive"))
      (node (ref "D11") (pin "1") (pinfunction "RA_1") (pintype "passive"))
    )
    (net (code "64") (name "Net-(D10-WA)") (class "Default")
      (node (ref "D10") (pin "7") (pinfunction "WA_7") (pintype "passive"))
      (node (ref "D3") (pin "8") (pinfunction "WC_8") (pintype "passive"))
    )
    (net (code "65") (name "Net-(D10-WC)") (class "Default")
      (node (ref "D10") (pin "8") (pinfunction "WC_8") (pintype "passive"))
      (node (ref "R14") (pin "1") (pinfunction "1_1") (pintype "passive"))
    )
    (net (code "66") (name "Net-(D11-BA)") (class "Default")
      (node (ref "D11") (pin "5") (pinfunction "BA_5") (pintype "passive"))
      (node (ref "R15") (pin "2") (pinfunction "2_2") (pintype "passive"))
    )
    (net (code "67") (name "Net-(D11-WA)") (class "Default")
      (node (ref "D11") (pin "7") (pinfunction "WA_7") (pintype "passive"))
      (node (ref "R14") (pin "2") (pinfunction "2_2") (pintype "passive"))
    )
    (net (code "68") (name "Net-(U1-EN)") (class "Default")
      (node (ref "R22") (pin "2") (pinfunction "2_2") (pintype "passive"))
      (node (ref "U1") (pin "5") (pinfunction "EN_5") (pintype "input"))
    )
    (net (code "69") (name "Net-(U1-SW)") (class "Default")
      (node (ref "C3") (pin "2") (pinfunction "2_2") (pintype "passive"))
      (node (ref "L1") (pin "1") (pinfunction "1_1") (pintype "passive"))
      (node (ref "U1") (pin "2") (pinfunction "SW_2") (pintype "power_in"))
    )
    (net (code "70") (name "Net-(U1-VBST)") (class "Default")
      (node (ref "C3") (pin "1") (pinfunction "1_1") (pintype "passive"))
      (node (ref "U1") (pin "6") (pinfunction "VBST_6") (pintype "power_in"))
    )
    (net (code "71") (name "Net-(U1-VFB)") (class "Default")
      (node (ref "R23") (pin "2") (pinfunction "2_2") (pintype "passive"))
      (node (ref "R24") (pin "1") (pinfunction "1_1") (pintype "passive"))
      (node (ref "U1") (pin "4") (pinfunction "VFB_4") (pintype "passive"))
    )
    (net (code "72") (name "Vin") (class "Default")
      (node (ref "C1") (pin "1") (pinfunction "1_1") (pintype "passive"))
      (node (ref "C7") (pin "2") (pinfunction "2_2") (pintype "passive"))
      (node (ref "C9") (pin "1") (pinfunction "1_1") (pintype "passive"))
      (node (ref "D3") (pin "1") (pinfunction "RA_1") (pintype "passive"))
      (node (ref "D3") (pin "3") (pinfunction "GA_3") (pintype "passive"))
      (node (ref "D3") (pin "5") (pinfunction "BA_5") (pintype "passive"))
      (node (ref "D3") (pin "7") (pinfunction "WA_7") (pintype "passive"))
      (node (ref "D4") (pin "1") (pinfunction "RA_1") (pintype "passive"))
      (node (ref "D4") (pin "3") (pinfunction "GA_3") (pintype "passive"))
      (node (ref "D4") (pin "5") (pinfunction "BA_5") (pintype "passive"))
      (node (ref "D4") (pin "7") (pinfunction "WA_7") (pintype "passive"))
      (node (ref "D5") (pin "1") (pinfunction "RA_1") (pintype "passive"))
      (node (ref "D5") (pin "3") (pinfunction "GA_3") (pintype "passive"))
      (node (ref "D5") (pin "5") (pinfunction "BA_5") (pintype "passive"))
      (node (ref "D5") (pin "7") (pinfunction "WA_7") (pintype "passive"))
      (node (ref "F1") (pin "1") (pinfunction "1_1") (pintype "passive"))
      (node (ref "J1") (pin "1") (pinfunction "1_1") (pintype "passive"))
      (node (ref "P2") (pin "6") (pinfunction "6_6") (pintype "passive"))
      (node (ref "P3") (pin "4") (pinfunction "4_4") (pintype "passive"))
      (node (ref "R22") (pin "1") (pinfunction "1_1") (pintype "passive"))
      (node (ref "U1") (pin "3") (pinfunction "IN_3") (pintype "power_in"))
      (node (ref "U2") (pin "3") (pinfunction "IN_3") (pintype "passive"))
    )
    (net (code "73") (name "unconnected-(U4-ALERT-Pad3)") (class "Default")
      (node (ref "U4") (pin "3") (pinfunction "ALERT_3") (pintype "output+no_connect"))
    )
    (net (code "74") (name "unconnected-(U5-N.C.-Pad2)") (class "Default")
      (node (ref "U5") (pin "2") (pinfunction "N.C._2") (pintype "passive+no_connect"))
    )
    (net (code "75") (name "unconnected-(U5-N.C.-Pad3)") (class "Default")
      (node (ref "U5") (pin "3") (pinfunction "N.C._3") (pintype "passive+no_connect"))
    )
    (net (code "76") (name "unconnected-(U5-N.C.-Pad5)") (class "Default")
      (node (ref "U5") (pin "5") (pinfunction "N.C._5") (pintype "passive+no_connect"))
    )
    (net (code "77") (name "unconnected-(U5-N.C.-Pad6)") (class "Default")
      (node (ref "U5") (pin "6") (pinfunction "N.C._6") (pintype "passive+no_connect"))
    )
    (net (code "78") (name "unconnected-(U5-N.C.-Pad7)") (class "Default")
      (node (ref "U5") (pin "7") (pinfunction "N.C._7") (pintype "passive+no_connect"))
    )
  )
)
